# MicroTeleinfo-V1_1.net
KiCad netlist of a schematic drawn in EAGLE
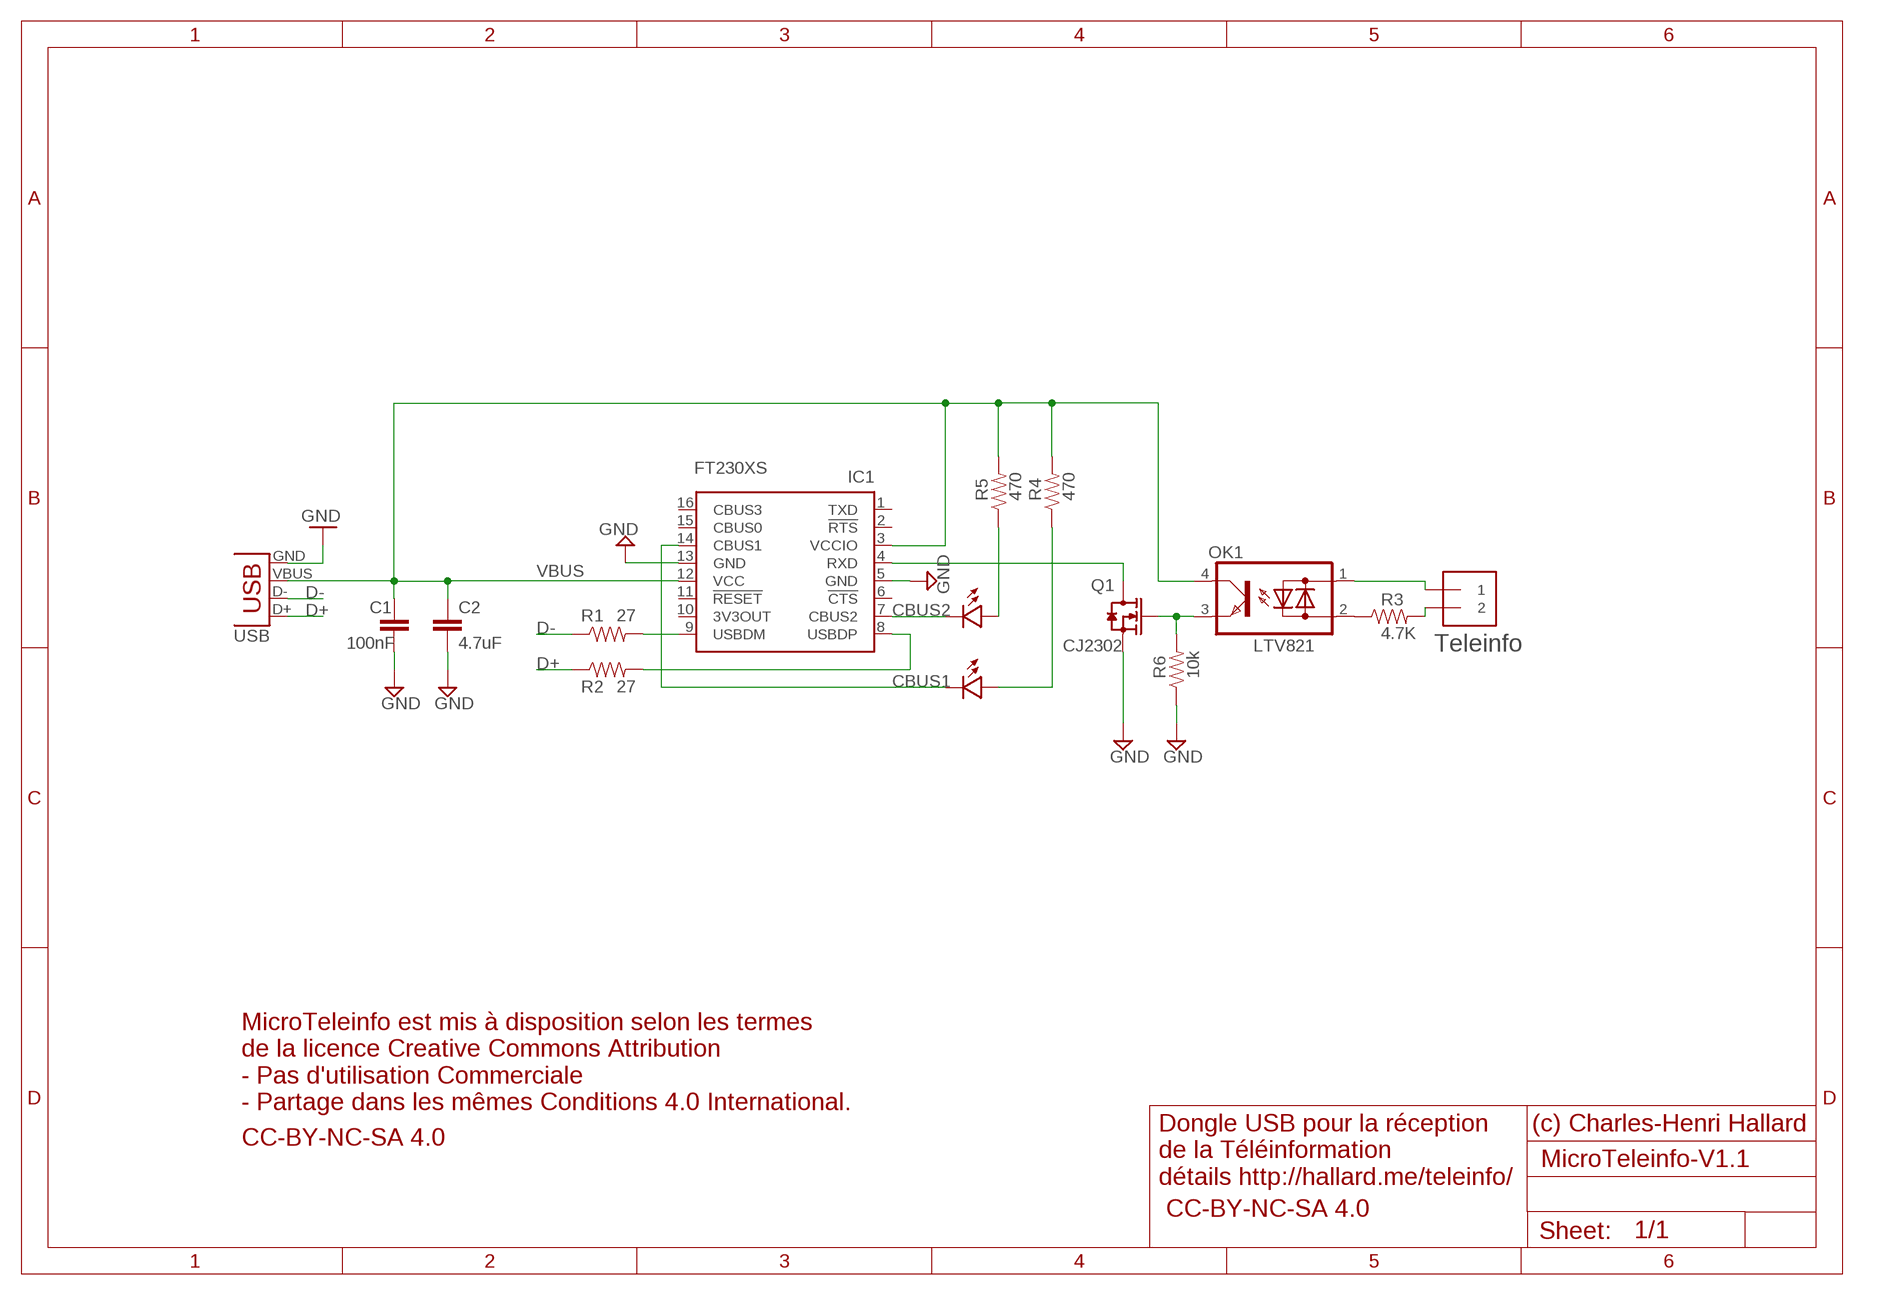
[diagram p0: schematic, sheet 1]

(export (version "E")
  (design (tool "Eeschema 10.0.6"))
  (components
    (comp (ref "C1")
      (value "100nF")
      (footprint "eagle-import:0603-CAP")
      (libsource (lib "eagle-import") (part "CAP0603-CAP"))
    )
    (comp (ref "C2")
      (value "4.7uF")
      (footprint "eagle-import:0805-CAP")
      (libsource (lib "eagle-import") (part "_c2h_CAP0805-CAP"))
    )
    (comp (ref "IC1")
      (value "FT230XS")
      (footprint "eagle-import:SSOP16")
      (libsource (lib "eagle-import") (part "FT230XS"))
    )
    (comp (ref "LED1")
      (value "Green")
      (footprint "eagle-import:0805-LED")
      (libsource (lib "eagle-import") (part "LED0805"))
    )
    (comp (ref "LED2")
      (value "Red")
      (footprint "eagle-import:0805-LED")
      (libsource (lib "eagle-import") (part "LED0805"))
    )
    (comp (ref "OK1")
      (value "LTV821")
      (footprint "eagle-import:DIL4-SMD")
      (fields (field (name "MF") "VISHAY/TELEFUNKEN") (field (name "MPN") "SFH6206-3"))
      (libsource (lib "eagle-import") (part "SFH6206"))
    )
    (comp (ref "Q1")
      (value "CJ2302")
      (footprint "eagle-import:SOT23")
      (libsource (lib "eagle-import") (part "MOSFET-N-''"))
    )
    (comp (ref "R1")
      (value "27")
      (footprint "eagle-import:0603-RES")
      (libsource (lib "eagle-import") (part "RESISTOR0603-RES"))
    )
    (comp (ref "R2")
      (value "27")
      (footprint "eagle-import:0603-RES")
      (libsource (lib "eagle-import") (part "RESISTOR0603-RES"))
    )
    (comp (ref "R3")
      (value "4.7K")
      (footprint "eagle-import:0805-RES")
      (libsource (lib "eagle-import") (part "_c2h_RESISTOR0805-RES"))
    )
    (comp (ref "R4")
      (value "470")
      (footprint "eagle-import:0603-RES")
      (libsource (lib "eagle-import") (part "RESISTOR0603-RES"))
    )
    (comp (ref "R5")
      (value "470")
      (footprint "eagle-import:0603-RES")
      (libsource (lib "eagle-import") (part "RESISTOR0603-RES"))
    )
    (comp (ref "R6")
      (value "10k")
      (footprint "eagle-import:0603-RES")
      (libsource (lib "eagle-import") (part "RESISTOR0603-RES"))
    )
    (comp (ref "TELEINFO")
      (value "1X2-3.5MM")
      (footprint "eagle-import:1X2-3.5MM")
      (libsource (lib "eagle-import") (part "1X2-3.5MM"))
    )
    (comp (ref "USB")
      (value "USBNOSILK")
      (footprint "eagle-import:USB-A-H_NO_SILK")
      (libsource (lib "eagle-import") (part "USBNOSILK"))
    )
  )
  (nets
    (net (code "1") (name "/CBUS1") (class "Default")
      (node (ref "IC1") (pin "14") (pinfunction "CBUS1_14") (pintype "bidirectional"))
      (node (ref "LED1") (pin "MINUS") (pinfunction "MINUS_MINUS") (pintype "passive"))
    )
    (net (code "2") (name "/CBUS2") (class "Default")
      (node (ref "IC1") (pin "7") (pinfunction "CBUS2_7") (pintype "bidirectional"))
      (node (ref "LED2") (pin "MINUS") (pinfunction "MINUS_MINUS") (pintype "passive"))
    )
    (net (code "3") (name "/D+") (class "Default")
      (node (ref "R2") (pin "1") (pinfunction "1_1") (pintype "passive"))
      (node (ref "USB") (pin "D+") (pinfunction "D+_D+") (pintype "bidirectional"))
    )
    (net (code "4") (name "/D-") (class "Default")
      (node (ref "R1") (pin "1") (pinfunction "1_1") (pintype "passive"))
      (node (ref "USB") (pin "D-") (pinfunction "D-_D-") (pintype "bidirectional"))
    )
    (net (code "5") (name "/VBUS") (class "Default")
      (node (ref "C1") (pin "1") (pinfunction "1_1") (pintype "passive"))
      (node (ref "C2") (pin "1") (pinfunction "1_1") (pintype "passive"))
      (node (ref "IC1") (pin "12") (pinfunction "VCC_12") (pintype "power_in"))
      (node (ref "IC1") (pin "3") (pinfunction "VCCIO_3") (pintype "power_in"))
      (node (ref "OK1") (pin "4") (pinfunction "C_4") (pintype "passive"))
      (node (ref "R4") (pin "2") (pinfunction "2_2") (pintype "passive"))
      (node (ref "R5") (pin "2") (pinfunction "2_2") (pintype "passive"))
      (node (ref "USB") (pin "VBUS") (pinfunction "VBUS_VBUS") (pintype "bidirectional"))
    )
    (net (code "6") (name "GND") (class "Default")
      (node (ref "C1") (pin "2") (pinfunction "2_2") (pintype "passive"))
      (node (ref "C2") (pin "2") (pinfunction "2_2") (pintype "passive"))
      (node (ref "IC1") (pin "13") (pinfunction "GND_13") (pintype "power_in"))
      (node (ref "IC1") (pin "5") (pinfunction "GND_5") (pintype "power_in"))
      (node (ref "Q1") (pin "2") (pinfunction "S_2") (pintype "passive"))
      (node (ref "R6") (pin "1") (pinfunction "1_1") (pintype "passive"))
      (node (ref "USB") (pin "GND") (pinfunction "GND_GND") (pintype "bidirectional"))
    )
    (net (code "7") (name "Net-(IC1-RXD)") (class "Default")
      (node (ref "IC1") (pin "4") (pinfunction "RXD_4") (pintype "input"))
      (node (ref "Q1") (pin "3") (pinfunction "D_3") (pintype "passive"))
    )
    (net (code "8") (name "Net-(IC1-USBDM)") (class "Default")
      (node (ref "IC1") (pin "9") (pinfunction "USBDM_9") (pintype "input"))
      (node (ref "R1") (pin "2") (pinfunction "2_2") (pintype "passive"))
    )
    (net (code "9") (name "Net-(IC1-USBDP)") (class "Default")
      (node (ref "IC1") (pin "8") (pinfunction "USBDP_8") (pintype "input"))
      (node (ref "R2") (pin "2") (pinfunction "2_2") (pintype "passive"))
    )
    (net (code "10") (name "Net-(LED1-PadPLUS)") (class "Default")
      (node (ref "LED1") (pin "PLUS") (pinfunction "PLUS_PLUS") (pintype "passive"))
      (node (ref "R4") (pin "1") (pinfunction "1_1") (pintype "passive"))
    )
    (net (code "11") (name "Net-(LED2-PadPLUS)") (class "Default")
      (node (ref "LED2") (pin "PLUS") (pinfunction "PLUS_PLUS") (pintype "passive"))
      (node (ref "R5") (pin "1") (pinfunction "1_1") (pintype "passive"))
    )
    (net (code "12") (name "Net-(OK1-AC1)") (class "Default")
      (node (ref "OK1") (pin "1") (pinfunction "AC1_1") (pintype "passive"))
      (node (ref "TELEINFO") (pin "1") (pinfunction "1_1") (pintype "passive"))
    )
    (net (code "13") (name "Net-(OK1-AC2)") (class "Default")
      (node (ref "OK1") (pin "2") (pinfunction "AC2_2") (pintype "passive"))
      (node (ref "R3") (pin "1") (pinfunction "1_1") (pintype "passive"))
    )
    (net (code "14") (name "Net-(OK1-E)") (class "Default")
      (node (ref "OK1") (pin "3") (pinfunction "E_3") (pintype "passive"))
      (node (ref "Q1") (pin "1") (pinfunction "G_1") (pintype "passive"))
      (node (ref "R6") (pin "2") (pinfunction "2_2") (pintype "passive"))
    )
    (net (code "15") (name "Net-(R3-Pad2)") (class "Default")
      (node (ref "R3") (pin "2") (pinfunction "2_2") (pintype "passive"))
      (node (ref "TELEINFO") (pin "2") (pinfunction "2_2") (pintype "passive"))
    )
    (net (code "16") (name "unconnected-(IC1-3V3OUT-Pad10)") (class "Default")
      (node (ref "IC1") (pin "10") (pinfunction "3V3OUT_10") (pintype "output"))
    )
    (net (code "17") (name "unconnected-(IC1-CBUS0-Pad15)") (class "Default")
      (node (ref "IC1") (pin "15") (pinfunction "CBUS0_15") (pintype "bidirectional"))
    )
    (net (code "18") (name "unconnected-(IC1-CBUS3-Pad16)") (class "Default")
      (node (ref "IC1") (pin "16") (pinfunction "CBUS3_16") (pintype "bidirectional"))
    )
    (net (code "19") (name "unconnected-(IC1-TXD-Pad1)") (class "Default")
      (node (ref "IC1") (pin "1") (pinfunction "TXD_1") (pintype "output"))
    )
    (net (code "20") (name "unconnected-(IC1-~{CTS}-Pad6)") (class "Default")
      (node (ref "IC1") (pin "6") (pinfunction "~{CTS}_6") (pintype "input"))
    )
    (net (code "21") (name "unconnected-(IC1-~{RESET}-Pad11)") (class "Default")
      (node (ref "IC1") (pin "11") (pinfunction "~{RESET}_11") (pintype "input"))
    )
    (net (code "22") (name "unconnected-(IC1-~{RTS}-Pad2)") (class "Default")
      (node (ref "IC1") (pin "2") (pinfunction "~{RTS}_2") (pintype "output"))
    )
  )
)
